# piezo-buffer-and-preamp-ritter_V0-1alt.net
KiCad netlist of a schematic drawn in EAGLE
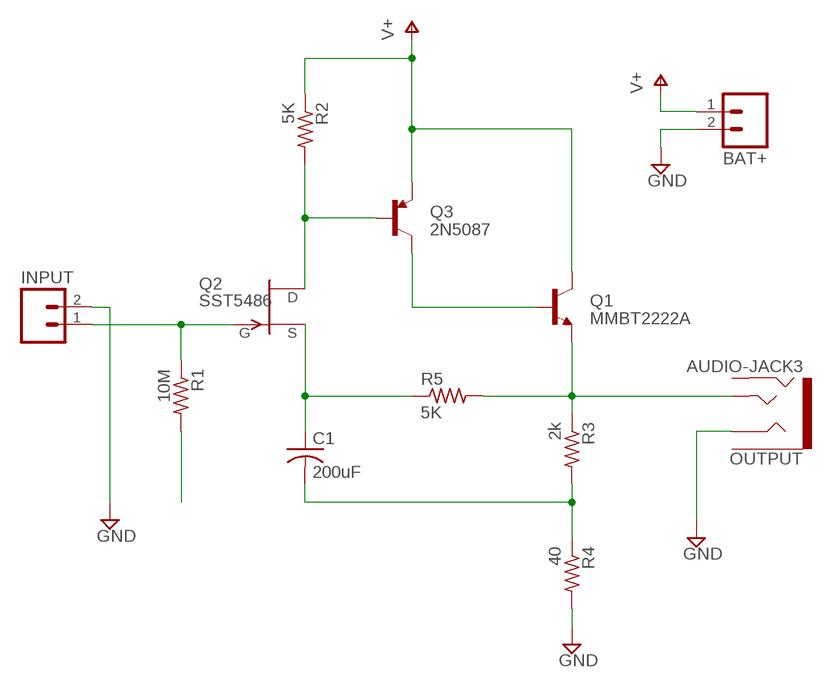
[diagram p0: schematic, sheet 1]

(export (version "E")
  (design (tool "Eeschema 10.0.6"))
  (components
    (comp (ref "BAT+")
      (value "M02LOCK")
      (footprint "eagle-import:1X02_LOCK")
      (libsource (lib "eagle-import") (part "M02LOCK"))
    )
    (comp (ref "C1")
      (value "200uF")
      (footprint "eagle-import:C0805")
      (libsource (lib "eagle-import") (part "C-USC0805"))
    )
    (comp (ref "INPUT")
      (value "M02LOCK")
      (footprint "eagle-import:1X02_LOCK")
      (libsource (lib "eagle-import") (part "M02LOCK"))
    )
    (comp (ref "OUTPUT")
      (value "AUDIO-JACK3")
      (footprint "eagle-import:AUDIO-JACK-TRRS-SMD")
      (libsource (lib "eagle-import") (part "AUDIO-JACK3"))
    )
    (comp (ref "Q1")
      (value "MMBT2222A")
      (footprint "eagle-import:SOT23")
      (libsource (lib "eagle-import") (part "TRANSISTOR_NPN"))
    )
    (comp (ref "Q2")
      (value "SST5486")
      (footprint "eagle-import:SOT23")
      (libsource (lib "eagle-import") (part "?548SST6"))
    )
    (comp (ref "Q3")
      (value "2N5087")
      (footprint "eagle-import:SOT23")
      (libsource (lib "eagle-import") (part "TRANSISTOR_PNP"))
    )
    (comp (ref "R1")
      (value "10M")
      (footprint "eagle-import:R0805")
      (libsource (lib "eagle-import") (part "R-US_R0805"))
    )
    (comp (ref "R2")
      (value "5K")
      (footprint "eagle-import:R0805")
      (libsource (lib "eagle-import") (part "R-US_R0805"))
    )
    (comp (ref "R3")
      (value "2k")
      (footprint "eagle-import:R0805")
      (libsource (lib "eagle-import") (part "R-US_R0805"))
    )
    (comp (ref "R4")
      (value "40")
      (footprint "eagle-import:R0805")
      (libsource (lib "eagle-import") (part "R-US_R0805"))
    )
    (comp (ref "R5")
      (value "5K")
      (footprint "eagle-import:R0805")
      (libsource (lib "eagle-import") (part "R-US_R0805"))
    )
  )
  (nets
    (net (code "1") (name "GND") (class "Default")
      (node (ref "BAT+") (pin "2") (pinfunction "2_2") (pintype "passive"))
      (node (ref "INPUT") (pin "2") (pinfunction "2_2") (pintype "passive"))
      (node (ref "OUTPUT") (pin "RING1") (pinfunction "RING1_RING1") (pintype "bidirectional"))
      (node (ref "R4") (pin "2") (pinfunction "2_2") (pintype "passive"))
    )
    (net (code "2") (name "Net-(C1-Pad2)") (class "Default")
      (node (ref "C1") (pin "2") (pinfunction "2_2") (pintype "passive"))
      (node (ref "R3") (pin "2") (pinfunction "2_2") (pintype "passive"))
      (node (ref "R4") (pin "1") (pinfunction "1_1") (pintype "passive"))
    )
    (net (code "3") (name "Net-(Q1-B)") (class "Default")
      (node (ref "Q1") (pin "1") (pinfunction "B_1") (pintype "passive"))
      (node (ref "Q3") (pin "3") (pinfunction "C_3") (pintype "passive"))
    )
    (net (code "4") (name "Net-(Q1-E)") (class "Default")
      (node (ref "OUTPUT") (pin "TIP") (pinfunction "TIP_TIP") (pintype "bidirectional"))
      (node (ref "Q1") (pin "2") (pinfunction "E_2") (pintype "passive"))
      (node (ref "R3") (pin "1") (pinfunction "1_1") (pintype "passive"))
      (node (ref "R5") (pin "2") (pinfunction "2_2") (pintype "passive"))
    )
    (net (code "5") (name "Net-(Q2-D)") (class "Default")
      (node (ref "Q2") (pin "1") (pinfunction "D_1") (pintype "passive"))
      (node (ref "Q3") (pin "1") (pinfunction "B_1") (pintype "passive"))
      (node (ref "R2") (pin "2") (pinfunction "2_2") (pintype "passive"))
    )
    (net (code "6") (name "Net-(Q2-G)") (class "Default")
      (node (ref "INPUT") (pin "1") (pinfunction "1_1") (pintype "passive"))
      (node (ref "Q2") (pin "3") (pinfunction "G_3") (pintype "passive"))
      (node (ref "R1") (pin "1") (pinfunction "1_1") (pintype "passive"))
    )
    (net (code "7") (name "Net-(Q2-S)") (class "Default")
      (node (ref "C1") (pin "1") (pinfunction "1_1") (pintype "passive"))
      (node (ref "Q2") (pin "2") (pinfunction "S_2") (pintype "passive"))
      (node (ref "R5") (pin "1") (pinfunction "1_1") (pintype "passive"))
    )
    (net (code "8") (name "V+") (class "Default")
      (node (ref "BAT+") (pin "1") (pinfunction "1_1") (pintype "passive"))
      (node (ref "Q1") (pin "3") (pinfunction "C_3") (pintype "passive"))
      (node (ref "Q3") (pin "2") (pinfunction "E_2") (pintype "passive"))
      (node (ref "R2") (pin "1") (pinfunction "1_1") (pintype "passive"))
    )
    (net (code "9") (name "unconnected-(OUTPUT-PadEARTH)") (class "Default")
      (node (ref "OUTPUT") (pin "EARTH") (pinfunction "EARTH_EARTH") (pintype "bidirectional"))
    )
    (net (code "10") (name "unconnected-(OUTPUT-PadRING2)") (class "Default")
      (node (ref "OUTPUT") (pin "RING2") (pinfunction "RING2_RING2") (pintype "bidirectional"))
    )
    (net (code "11") (name "unconnected-(R1-Pad2)") (class "Default")
      (node (ref "R1") (pin "2") (pinfunction "2_2") (pintype "passive"))
    )
  )
)
